# Sheet2.net
KiCad netlist of a schematic drawn in Altium Designer
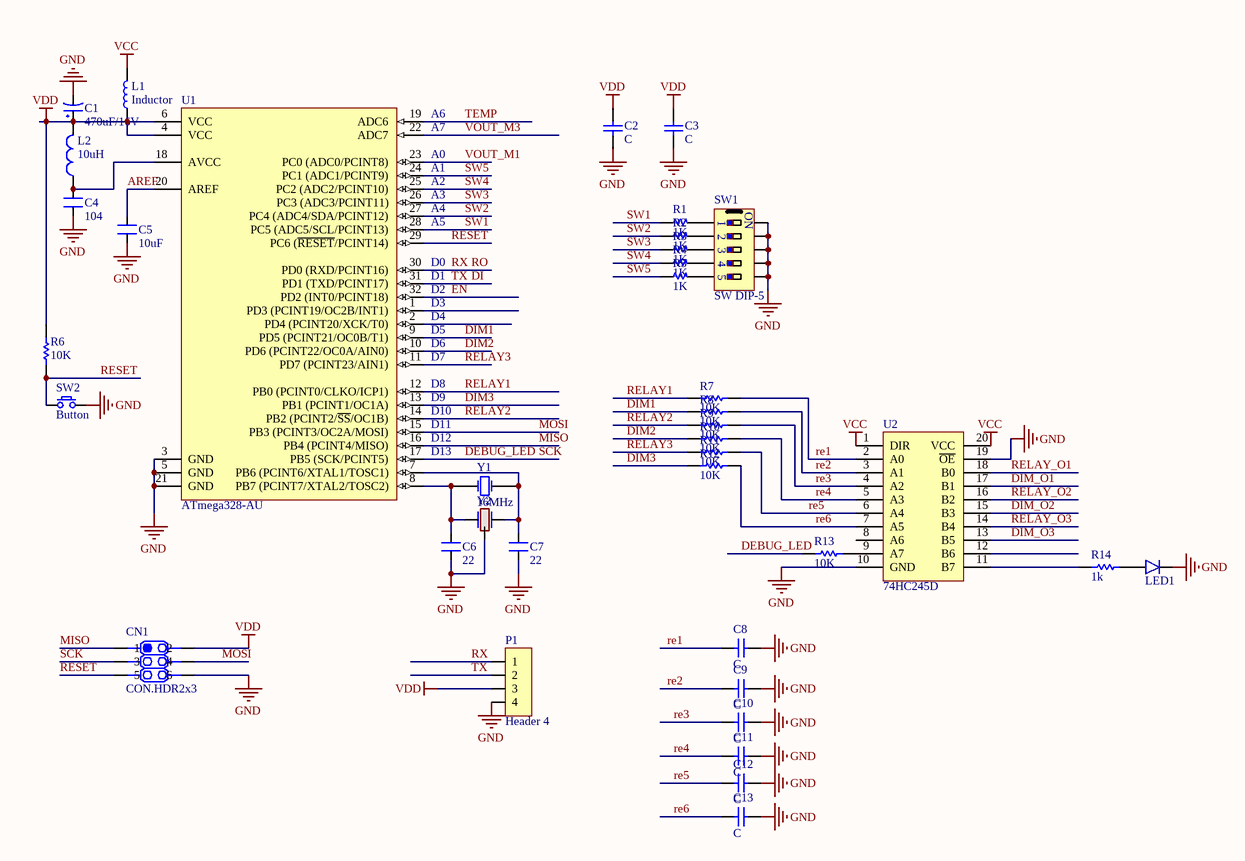
[diagram p0: Sheet2.SchDoc]

(export (version "E")
  (design (tool "Eeschema 10.0.6"))
  (components
    (comp (ref "C1")
      (value "470uF/16V")
      (footprint "WCAP-PSHP 8x8.7x3.1")
      (description "Cap 1000uF/16V - 220uF/50V")
      (libsource (lib "syhaunguyen") (part "CP4"))
    )
    (comp (ref "C2")
      (value "C")
      (footprint "C 0805 (2012)")
      (description "Capacitor non-pol")
      (libsource (lib "BKIT4U_LIB") (part "Capacitor NP"))
    )
    (comp (ref "C3")
      (value "C")
      (footprint "C 0805 (2012)")
      (description "Capacitor non-pol")
      (libsource (lib "BKIT4U_LIB") (part "Capacitor NP"))
    )
    (comp (ref "C4")
      (value "104")
      (footprint "R 0805 (2012)")
      (description "Cap np 104 => 105pF")
      (libsource (lib "syhaunguyen") (part "CN2"))
    )
    (comp (ref "C5")
      (value "10uF")
      (footprint "R 0805 (2012)")
      (description "Cap np  1pF - 472pF")
      (libsource (lib "syhaunguyen") (part "CN1"))
    )
    (comp (ref "C6")
      (value "22")
      (footprint "C 0805 (2012)")
      (description "Cap np 104 => 105pF")
      (libsource (lib "syhaunguyen") (part "CN2"))
    )
    (comp (ref "C7")
      (value "22")
      (footprint "C 0805 (2012)")
      (description "Cap np 104 => 105pF")
      (libsource (lib "syhaunguyen") (part "CN2"))
    )
    (comp (ref "C8")
      (value "C")
      (footprint "C 0805")
      (description "Capacitor non-pol")
      (libsource (lib "chipfc_altium_libs") (part "Capacitor NP"))
    )
    (comp (ref "C9")
      (value "C")
      (footprint "C 0805")
      (description "Capacitor non-pol")
      (libsource (lib "chipfc_altium_libs") (part "Capacitor NP"))
    )
    (comp (ref "C10")
      (value "C")
      (footprint "C 0805")
      (description "Capacitor non-pol")
      (libsource (lib "chipfc_altium_libs") (part "Capacitor NP"))
    )
    (comp (ref "C11")
      (value "C")
      (footprint "C 0805")
      (description "Capacitor non-pol")
      (libsource (lib "chipfc_altium_libs") (part "Capacitor NP"))
    )
    (comp (ref "C12")
      (value "C")
      (footprint "C 0805")
      (description "Capacitor non-pol")
      (libsource (lib "chipfc_altium_libs") (part "Capacitor NP"))
    )
    (comp (ref "C13")
      (value "C")
      (footprint "C 0805")
      (description "Capacitor non-pol")
      (libsource (lib "chipfc_altium_libs") (part "Capacitor NP"))
    )
    (comp (ref "CN1")
      (value "CON.HDR2x3")
      (footprint "Header 3x2")
      (description "Header 2x3")
      (fields (field (name "PUBLISHER") "Hoang Nguyen"))
      (libsource (lib "phong") (part "CON.HDR2x3"))
    )
    (comp (ref "L1")
      (value "Inductor")
      (footprint "Inductor SMD 0805 (2012)")
      (libsource (lib "BKIT4U_LIB") (part "Inductor"))
    )
    (comp (ref "L2")
      (value "10uH")
      (footprint "R 0805 (2012)")
      (description "Inductor")
      (libsource (lib "syhaunguyen") (part "L1"))
    )
    (comp (ref "LED1")
      (value "Led")
      (footprint "Led SMD 0805")
      (description "Typical LED")
      (libsource (lib "BKIT4U_LIB") (part "Led"))
    )
    (comp (ref "P1")
      (value "Header 4")
      (footprint "Header 4")
      (description "Header, 4-Pin")
      (libsource (lib "BKIT4U_LIB") (part "Header 4"))
    )
    (comp (ref "R1")
      (value "1K")
      (footprint "R 0805")
      (description "Resistor")
      (libsource (lib "chipfc_altium_libs") (part "Resistor"))
    )
    (comp (ref "R2")
      (value "1K")
      (footprint "R 0805")
      (description "Resistor")
      (libsource (lib "chipfc_altium_libs") (part "Resistor"))
    )
    (comp (ref "R3")
      (value "1K")
      (footprint "R 0805")
      (description "Resistor")
      (libsource (lib "chipfc_altium_libs") (part "Resistor"))
    )
    (comp (ref "R4")
      (value "1K")
      (footprint "R 0805")
      (description "Resistor")
      (libsource (lib "chipfc_altium_libs") (part "Resistor"))
    )
    (comp (ref "R5")
      (value "1K")
      (footprint "R 0805")
      (description "Resistor")
      (libsource (lib "chipfc_altium_libs") (part "Resistor"))
    )
    (comp (ref "R6")
      (value "10K")
      (footprint "R 0805 (2012)")
      (description "Resistor")
      (fields (field (name "PUBLISHER") "Altium Limited"))
      (libsource (lib "phong") (part "Resistor"))
    )
    (comp (ref "R7")
      (value "10K")
      (footprint "R 0805 (2012)")
      (description "Resistor")
      (fields (field (name "PUBLISHER") "Altium Limited"))
      (libsource (lib "BKIT4U_LIB") (part "Resistor"))
    )
    (comp (ref "R8")
      (value "10K")
      (footprint "R 0805 (2012)")
      (description "Resistor")
      (fields (field (name "PUBLISHER") "Altium Limited"))
      (libsource (lib "BKIT4U_LIB") (part "Resistor"))
    )
    (comp (ref "R9")
      (value "10K")
      (footprint "R 0805 (2012)")
      (description "Resistor")
      (fields (field (name "PUBLISHER") "Altium Limited"))
      (libsource (lib "BKIT4U_LIB") (part "Resistor"))
    )
    (comp (ref "R10")
      (value "10K")
      (footprint "R 0805 (2012)")
      (description "Resistor")
      (fields (field (name "PUBLISHER") "Altium Limited"))
      (libsource (lib "BKIT4U_LIB") (part "Resistor"))
    )
    (comp (ref "R11")
      (value "10K")
      (footprint "R 0805 (2012)")
      (description "Resistor")
      (fields (field (name "PUBLISHER") "Altium Limited"))
      (libsource (lib "BKIT4U_LIB") (part "Resistor"))
    )
    (comp (ref "R12")
      (value "10K")
      (footprint "R 0805 (2012)")
      (description "Resistor")
      (fields (field (name "PUBLISHER") "Altium Limited"))
      (libsource (lib "BKIT4U_LIB") (part "Resistor"))
    )
    (comp (ref "R13")
      (value "10K")
      (footprint "R 0805 (2012)")
      (description "Resistor")
      (fields (field (name "PUBLISHER") "Altium Limited"))
      (libsource (lib "BKIT4U_LIB") (part "Resistor"))
    )
    (comp (ref "R14")
      (value "1k")
      (footprint "R 0805 (2012)")
      (description "Resistor")
      (fields (field (name "PUBLISHER") "Altium Limited"))
      (libsource (lib "BKIT4U_LIB") (part "Resistor"))
    )
    (comp (ref "SW1")
      (value "SW DIP-5")
      (footprint "SW/DIP5/300")
      (libsource (lib "chipfc_altium_libs") (part "SW DIP-5"))
    )
    (comp (ref "SW2")
      (value "Button")
      (footprint "SW/2/SMD")
      (description "Tact switch 2 pin")
      (libsource (lib "BKIT4U_LIB") (part "SW SPST"))
    )
    (comp (ref "U1")
      (value "ATmega328-AU")
      (footprint "QFP32N")
      (fields (field (name "PUBLISHER") "Altium Limited"))
      (libsource (lib "Atmel Microcontroller 8-Bit megaAVR") (part "ATmega328-AU"))
    )
    (comp (ref "U2")
      (value "74HC245D")
      (footprint "SOIC-20")
      (description "IC TRANSCVR NON-INVERT 6V 20SO")
      (libsource (lib "chipfc_altium_libs") (part "74HC245D"))
    )
    (comp (ref "Y1")
      (value "16MHz")
      (footprint "XTAL")
      (description "Crystal Oscillator")
      (fields (field (name "PUBLISHER") "Altium Limited"))
      (libsource (lib "phong") (part "XTAL"))
    )
    (comp (ref "Y2")
      (value "~")
      (footprint "Crystal SMD CSTCE")
      (libsource (lib "BKIT4U_LIB") (part "Crystal CSTCE"))
    )
  )
  (nets
    (net (code "1") (name "/AREF") (class "Default")
      (node (ref "C5") (pin "2") (pinfunction "2_2") (pintype "passive"))
      (node (ref "U1") (pin "20") (pinfunction "AREF_20") (pintype "passive"))
    )
    (net (code "2") (name "/DEBUG_LED") (class "Default")
      (node (ref "CN1") (pin "3") (pinfunction "3_3") (pintype "passive"))
      (node (ref "R13") (pin "1") (pinfunction "1_1") (pintype "passive"))
      (node (ref "U1") (pin "17") (pinfunction "PB5_(SCK/PCINT5)_17") (pintype "bidirectional"))
    )
    (net (code "3") (name "/DI") (class "Default")
      (node (ref "P1") (pin "2") (pinfunction "2_2") (pintype "passive"))
      (node (ref "U1") (pin "31") (pinfunction "PD1_(TXD/PCINT17)_31") (pintype "bidirectional"))
    )
    (net (code "4") (name "/DIM1") (class "Default")
      (node (ref "R8") (pin "1") (pinfunction "1_1") (pintype "passive"))
      (node (ref "U1") (pin "9") (pinfunction "PD5_(PCINT21/OC0B/T1)_9") (pintype "bidirectional"))
    )
    (net (code "5") (name "/DIM2") (class "Default")
      (node (ref "R10") (pin "1") (pinfunction "1_1") (pintype "passive"))
      (node (ref "U1") (pin "10") (pinfunction "PD6_(PCINT22/OC0A/AIN0)_10") (pintype "bidirectional"))
    )
    (net (code "6") (name "/DIM3") (class "Default")
      (node (ref "R12") (pin "1") (pinfunction "1_1") (pintype "passive"))
      (node (ref "U1") (pin "13") (pinfunction "PB1_(PCINT1/OC1A)_13") (pintype "bidirectional"))
    )
    (net (code "7") (name "/DIM_O1") (class "Default")
      (node (ref "U2") (pin "17") (pinfunction "B1_17") (pintype "passive"))
    )
    (net (code "8") (name "/DIM_O2") (class "Default")
      (node (ref "U2") (pin "15") (pinfunction "B3_15") (pintype "passive"))
    )
    (net (code "9") (name "/DIM_O3") (class "Default")
      (node (ref "U2") (pin "13") (pinfunction "B5_13") (pintype "passive"))
    )
    (net (code "10") (name "/EN") (class "Default")
      (node (ref "U1") (pin "32") (pinfunction "PD2_(INT0/PCINT18)_32") (pintype "bidirectional"))
    )
    (net (code "11") (name "/MISO") (class "Default")
      (node (ref "CN1") (pin "1") (pinfunction "1_1") (pintype "passive"))
      (node (ref "U1") (pin "16") (pinfunction "PB4_(PCINT4/MISO)_16") (pintype "bidirectional"))
    )
    (net (code "12") (name "/MOSI") (class "Default")
      (node (ref "CN1") (pin "4") (pinfunction "4_4") (pintype "passive"))
      (node (ref "U1") (pin "15") (pinfunction "PB3_(PCINT3/OC2A/MOSI)_15") (pintype "bidirectional"))
    )
    (net (code "13") (name "/RELAY1") (class "Default")
      (node (ref "R7") (pin "1") (pinfunction "1_1") (pintype "passive"))
      (node (ref "U1") (pin "12") (pinfunction "PB0_(PCINT0/CLKO/ICP1)_12") (pintype "bidirectional"))
    )
    (net (code "14") (name "/RELAY2") (class "Default")
      (node (ref "R9") (pin "1") (pinfunction "1_1") (pintype "passive"))
      (node (ref "U1") (pin "14") (pinfunction "PB2_(PCINT2/~{SS}/OC1B)_14") (pintype "bidirectional"))
    )
    (net (code "15") (name "/RELAY3") (class "Default")
      (node (ref "R11") (pin "1") (pinfunction "1_1") (pintype "passive"))
      (node (ref "U1") (pin "11") (pinfunction "PD7_(PCINT23/AIN1)_11") (pintype "bidirectional"))
    )
    (net (code "16") (name "/RELAY_O1") (class "Default")
      (node (ref "U2") (pin "18") (pinfunction "B0_18") (pintype "passive"))
    )
    (net (code "17") (name "/RELAY_O2") (class "Default")
      (node (ref "U2") (pin "16") (pinfunction "B2_16") (pintype "passive"))
    )
    (net (code "18") (name "/RELAY_O3") (class "Default")
      (node (ref "U2") (pin "14") (pinfunction "B4_14") (pintype "passive"))
    )
    (net (code "19") (name "/RESET") (class "Default")
      (node (ref "CN1") (pin "5") (pinfunction "5_5") (pintype "passive"))
      (node (ref "R6") (pin "1") (pinfunction "1_1") (pintype "passive"))
      (node (ref "SW2") (pin "1") (pinfunction "1_1") (pintype "passive"))
      (node (ref "U1") (pin "29") (pinfunction "PC6_(~{RESET}/PCINT14)_29") (pintype "bidirectional"))
    )
    (net (code "20") (name "/RO") (class "Default")
      (node (ref "P1") (pin "1") (pinfunction "1_1") (pintype "passive"))
      (node (ref "U1") (pin "30") (pinfunction "PD0_(RXD/PCINT16)_30") (pintype "bidirectional"))
    )
    (net (code "21") (name "/SW1") (class "Default")
      (node (ref "R1") (pin "1") (pinfunction "1_1") (pintype "passive"))
      (node (ref "U1") (pin "28") (pinfunction "PC5_(ADC5/SCL/PCINT13)_28") (pintype "bidirectional"))
    )
    (net (code "22") (name "/SW2") (class "Default")
      (node (ref "R2") (pin "1") (pinfunction "1_1") (pintype "passive"))
      (node (ref "U1") (pin "27") (pinfunction "PC4_(ADC4/SDA/PCINT12)_27") (pintype "bidirectional"))
    )
    (net (code "23") (name "/SW3") (class "Default")
      (node (ref "R3") (pin "1") (pinfunction "1_1") (pintype "passive"))
      (node (ref "U1") (pin "26") (pinfunction "PC3_(ADC3/PCINT11)_26") (pintype "bidirectional"))
    )
    (net (code "24") (name "/SW4") (class "Default")
      (node (ref "R4") (pin "1") (pinfunction "1_1") (pintype "passive"))
      (node (ref "U1") (pin "25") (pinfunction "PC2_(ADC2/PCINT10)_25") (pintype "bidirectional"))
    )
    (net (code "25") (name "/SW5") (class "Default")
      (node (ref "R5") (pin "1") (pinfunction "1_1") (pintype "passive"))
      (node (ref "U1") (pin "24") (pinfunction "PC1_(ADC1/PCINT9)_24") (pintype "bidirectional"))
    )
    (net (code "26") (name "/TEMP") (class "Default")
      (node (ref "U1") (pin "19") (pinfunction "ADC6_19") (pintype "input"))
    )
    (net (code "27") (name "/VOUT_M1") (class "Default")
      (node (ref "U1") (pin "23") (pinfunction "PC0_(ADC0/PCINT8)_23") (pintype "bidirectional"))
    )
    (net (code "28") (name "/VOUT_M3") (class "Default")
      (node (ref "U1") (pin "22") (pinfunction "ADC7_22") (pintype "input"))
    )
    (net (code "29") (name "/re1") (class "Default")
      (node (ref "C8") (pin "1") (pinfunction "1_1") (pintype "passive"))
      (node (ref "R7") (pin "2") (pinfunction "2_2") (pintype "passive"))
      (node (ref "U2") (pin "2") (pinfunction "A0_2") (pintype "passive"))
    )
    (net (code "30") (name "/re2") (class "Default")
      (node (ref "C9") (pin "1") (pinfunction "1_1") (pintype "passive"))
      (node (ref "R8") (pin "2") (pinfunction "2_2") (pintype "passive"))
      (node (ref "U2") (pin "3") (pinfunction "A1_3") (pintype "passive"))
    )
    (net (code "31") (name "/re3") (class "Default")
      (node (ref "C10") (pin "1") (pinfunction "1_1") (pintype "passive"))
      (node (ref "R9") (pin "2") (pinfunction "2_2") (pintype "passive"))
      (node (ref "U2") (pin "4") (pinfunction "A2_4") (pintype "passive"))
    )
    (net (code "32") (name "/re4") (class "Default")
      (node (ref "C11") (pin "1") (pinfunction "1_1") (pintype "passive"))
      (node (ref "R10") (pin "2") (pinfunction "2_2") (pintype "passive"))
      (node (ref "U2") (pin "5") (pinfunction "A3_5") (pintype "passive"))
    )
    (net (code "33") (name "/re5") (class "Default")
      (node (ref "C12") (pin "1") (pinfunction "1_1") (pintype "passive"))
      (node (ref "R11") (pin "2") (pinfunction "2_2") (pintype "passive"))
      (node (ref "U2") (pin "6") (pinfunction "A4_6") (pintype "passive"))
    )
    (net (code "34") (name "/re6") (class "Default")
      (node (ref "C13") (pin "1") (pinfunction "1_1") (pintype "passive"))
      (node (ref "R12") (pin "2") (pinfunction "2_2") (pintype "passive"))
      (node (ref "U2") (pin "7") (pinfunction "A5_7") (pintype "passive"))
    )
    (net (code "35") (name "GND") (class "Default")
      (node (ref "C1") (pin "2") (pinfunction "2_2") (pintype "passive"))
      (node (ref "C10") (pin "2") (pinfunction "2_2") (pintype "passive"))
      (node (ref "C11") (pin "2") (pinfunction "2_2") (pintype "passive"))
      (node (ref "C12") (pin "2") (pinfunction "2_2") (pintype "passive"))
      (node (ref "C13") (pin "2") (pinfunction "2_2") (pintype "passive"))
      (node (ref "C2") (pin "2") (pinfunction "2_2") (pintype "passive"))
      (node (ref "C3") (pin "2") (pinfunction "2_2") (pintype "passive"))
      (node (ref "C4") (pin "1") (pinfunction "1_1") (pintype "passive"))
      (node (ref "C5") (pin "1") (pinfunction "1_1") (pintype "passive"))
      (node (ref "C6") (pin "1") (pinfunction "1_1") (pintype "passive"))
      (node (ref "C7") (pin "1") (pinfunction "1_1") (pintype "passive"))
      (node (ref "C8") (pin "2") (pinfunction "2_2") (pintype "passive"))
      (node (ref "C9") (pin "2") (pinfunction "2_2") (pintype "passive"))
      (node (ref "CN1") (pin "6") (pinfunction "6_6") (pintype "passive"))
      (node (ref "LED1") (pin "2") (pinfunction "K_2") (pintype "passive"))
      (node (ref "P1") (pin "4") (pinfunction "4_4") (pintype "passive"))
      (node (ref "SW1") (pin "10") (pinfunction "10_10") (pintype "passive"))
      (node (ref "SW1") (pin "6") (pinfunction "6_6") (pintype "passive"))
      (node (ref "SW1") (pin "7") (pinfunction "7_7") (pintype "passive"))
      (node (ref "SW1") (pin "8") (pinfunction "8_8") (pintype "passive"))
      (node (ref "SW1") (pin "9") (pinfunction "9_9") (pintype "passive"))
      (node (ref "SW2") (pin "2") (pinfunction "2_2") (pintype "passive"))
      (node (ref "U1") (pin "21") (pinfunction "GND_21") (pintype "power_in"))
      (node (ref "U1") (pin "3") (pinfunction "GND_3") (pintype "power_in"))
      (node (ref "U1") (pin "5") (pinfunction "GND_5") (pintype "power_in"))
      (node (ref "U2") (pin "10") (pinfunction "GND_10") (pintype "passive"))
      (node (ref "U2") (pin "19") (pinfunction "~{OE}_19") (pintype "passive"))
      (node (ref "Y2") (pin "2") (pinfunction "2_2") (pintype "passive"))
    )
    (net (code "36") (name "Net-(LED1-A)") (class "Default")
      (node (ref "LED1") (pin "1") (pinfunction "A_1") (pintype "passive"))
      (node (ref "R14") (pin "2") (pinfunction "2_2") (pintype "passive"))
    )
    (net (code "37") (name "Net-(R1-Pad2)") (class "Default")
      (node (ref "R1") (pin "2") (pinfunction "2_2") (pintype "passive"))
      (node (ref "SW1") (pin "1") (pinfunction "1_1") (pintype "passive"))
    )
    (net (code "38") (name "Net-(R2-Pad2)") (class "Default")
      (node (ref "R2") (pin "2") (pinfunction "2_2") (pintype "passive"))
      (node (ref "SW1") (pin "2") (pinfunction "2_2") (pintype "passive"))
    )
    (net (code "39") (name "Net-(R3-Pad2)") (class "Default")
      (node (ref "R3") (pin "2") (pinfunction "2_2") (pintype "passive"))
      (node (ref "SW1") (pin "3") (pinfunction "3_3") (pintype "passive"))
    )
    (net (code "40") (name "Net-(R4-Pad2)") (class "Default")
      (node (ref "R4") (pin "2") (pinfunction "2_2") (pintype "passive"))
      (node (ref "SW1") (pin "4") (pinfunction "4_4") (pintype "passive"))
    )
    (net (code "41") (name "Net-(R5-Pad2)") (class "Default")
      (node (ref "R5") (pin "2") (pinfunction "2_2") (pintype "passive"))
      (node (ref "SW1") (pin "5") (pinfunction "5_5") (pintype "passive"))
    )
    (net (code "42") (name "Net-(U1-AVCC)") (class "Default")
      (node (ref "C4") (pin "2") (pinfunction "2_2") (pintype "passive"))
      (node (ref "L2") (pin "1") (pinfunction "1_1") (pintype "passive"))
      (node (ref "U1") (pin "18") (pinfunction "AVCC_18") (pintype "power_in"))
    )
    (net (code "43") (name "Net-(U1-PB6_(PCINT6{slash}XTAL1{slash}TOSC1))") (class "Default")
      (node (ref "C7") (pin "2") (pinfunction "2_2") (pintype "passive"))
      (node (ref "U1") (pin "7") (pinfunction "PB6_(PCINT6/XTAL1/TOSC1)_7") (pintype "bidirectional"))
      (node (ref "Y1") (pin "2") (pinfunction "OSC2_2") (pintype "passive"))
      (node (ref "Y2") (pin "1") (pinfunction "1_1") (pintype "passive"))
    )
    (net (code "44") (name "Net-(U1-PB7_(PCINT7{slash}XTAL2{slash}TOSC2))") (class "Default")
      (node (ref "C6") (pin "2") (pinfunction "2_2") (pintype "passive"))
      (node (ref "U1") (pin "8") (pinfunction "PB7_(PCINT7/XTAL2/TOSC2)_8") (pintype "bidirectional"))
      (node (ref "Y1") (pin "1") (pinfunction "OSC1_1") (pintype "passive"))
      (node (ref "Y2") (pin "3") (pinfunction "3_3") (pintype "passive"))
    )
    (net (code "45") (name "Net-(U2-A7)") (class "Default")
      (node (ref "R13") (pin "2") (pinfunction "2_2") (pintype "passive"))
      (node (ref "U2") (pin "9") (pinfunction "A7_9") (pintype "passive"))
    )
    (net (code "46") (name "Net-(U2-B7)") (class "Default")
      (node (ref "R14") (pin "1") (pinfunction "1_1") (pintype "passive"))
      (node (ref "U2") (pin "11") (pinfunction "B7_11") (pintype "passive"))
    )
    (net (code "47") (name "VCC") (class "Default")
      (node (ref "L1") (pin "2") (pinfunction "2_2") (pintype "passive"))
      (node (ref "U2") (pin "1") (pinfunction "DIR_1") (pintype "passive"))
      (node (ref "U2") (pin "20") (pinfunction "VCC_20") (pintype "passive"))
    )
    (net (code "48") (name "VDD") (class "Default")
      (node (ref "C1") (pin "1") (pinfunction "1_1") (pintype "passive"))
      (node (ref "C2") (pin "1") (pinfunction "1_1") (pintype "passive"))
      (node (ref "C3") (pin "1") (pinfunction "1_1") (pintype "passive"))
      (node (ref "CN1") (pin "2") (pinfunction "2_2") (pintype "passive"))
      (node (ref "L1") (pin "1") (pinfunction "1_1") (pintype "passive"))
      (node (ref "L2") (pin "2") (pinfunction "2_2") (pintype "passive"))
      (node (ref "P1") (pin "3") (pinfunction "3_3") (pintype "passive"))
      (node (ref "R6") (pin "2") (pinfunction "2_2") (pintype "passive"))
      (node (ref "U1") (pin "4") (pinfunction "VCC_4") (pintype "power_in"))
      (node (ref "U1") (pin "6") (pinfunction "VCC_6") (pintype "power_in"))
    )
    (net (code "49") (name "unconnected-(U1-PD3_(PCINT19{slash}OC2B{slash}INT1)-Pad1)") (class "Default")
      (node (ref "U1") (pin "1") (pinfunction "PD3_(PCINT19/OC2B/INT1)_1") (pintype "bidirectional"))
    )
    (net (code "50") (name "unconnected-(U1-PD4_(PCINT20{slash}XCK{slash}T0)-Pad2)") (class "Default")
      (node (ref "U1") (pin "2") (pinfunction "PD4_(PCINT20/XCK/T0)_2") (pintype "bidirectional"))
    )
    (net (code "51") (name "unconnected-(U2-A6-Pad8)") (class "Default")
      (node (ref "U2") (pin "8") (pinfunction "A6_8") (pintype "passive"))
    )
    (net (code "52") (name "unconnected-(U2-B6-Pad12)") (class "Default")
      (node (ref "U2") (pin "12") (pinfunction "B6_12") (pintype "passive"))
    )
  )
)
